# STM32_Nucleo_144.net
KiCad netlist of a schematic drawn in Altium Designer
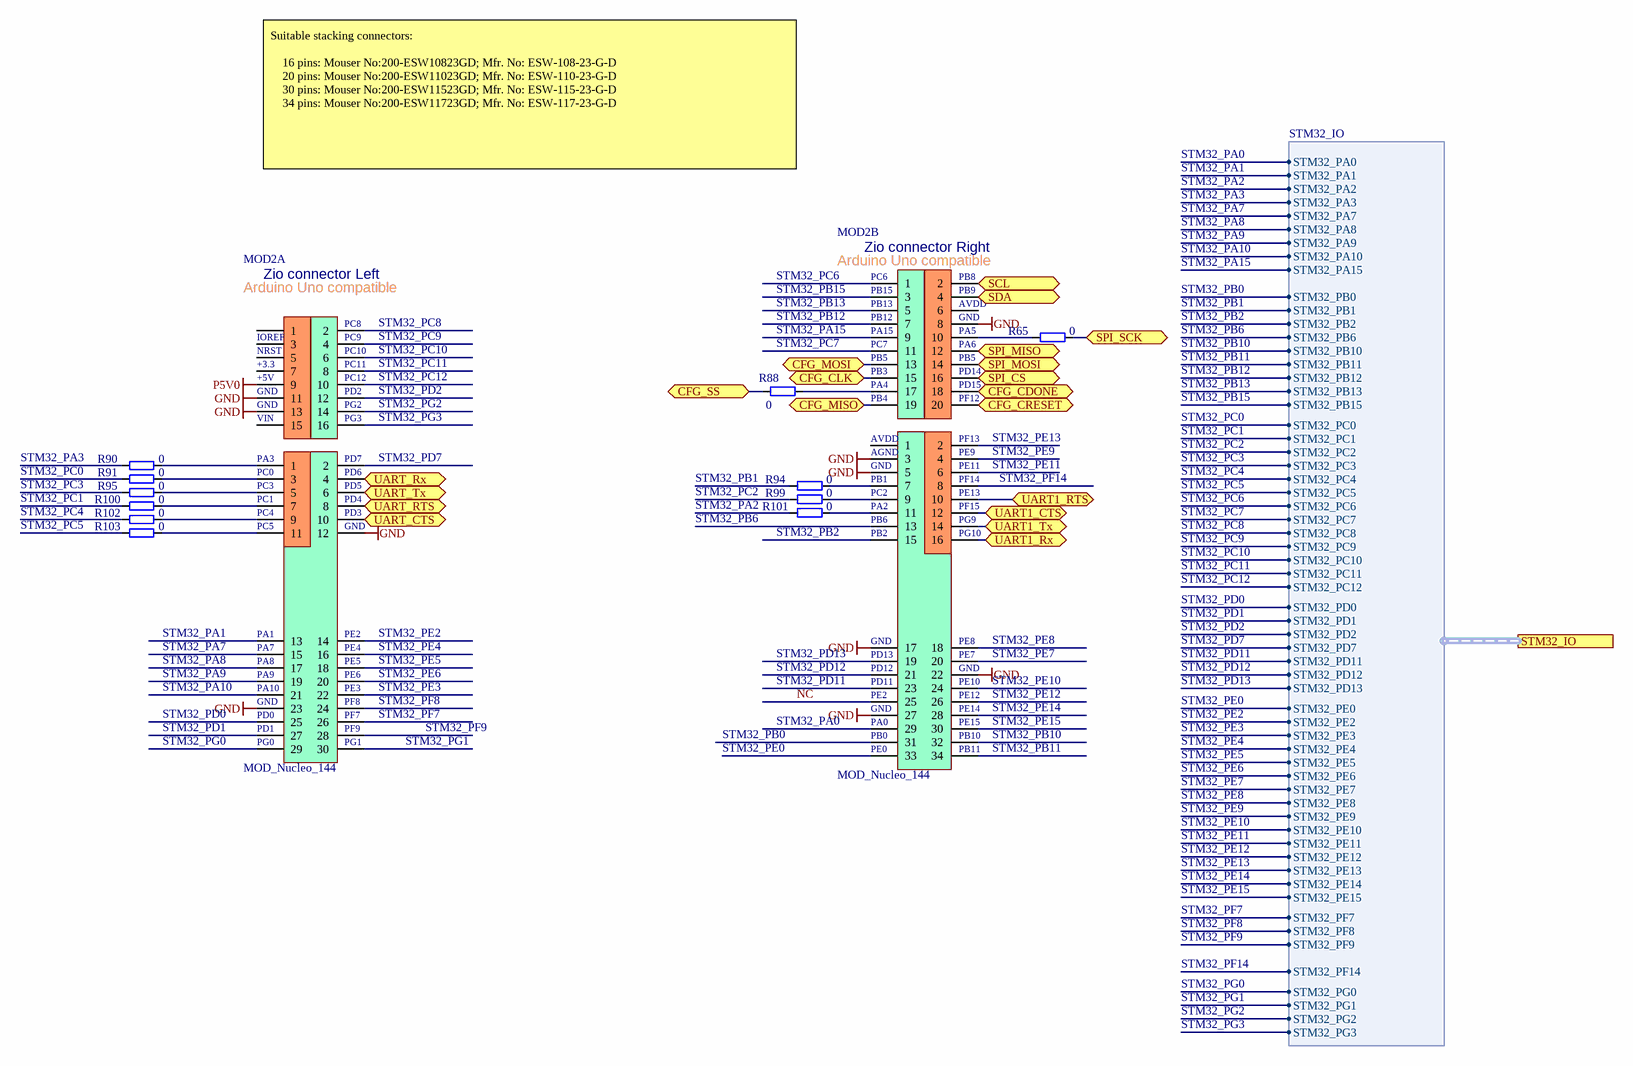
[diagram p0: STM32_Nucleo_144.SchDoc]

(export (version "E")
  (design (tool "Eeschema 10.0.6"))
  (components
    (comp (ref "MOD2")
      (value "MOD_Nucleo_144")
      (footprint "MOD_STM32_Nucleo_144")
      (libsource (lib "LIBRARY_SCH") (part "MOD_Nucleo_144"))
    )
    (comp (ref "R65")
      (value "0")
      (footprint "RESC1608X55N")
      (description "Resistor")
      (fields
        (field (name "PART NUMBER") "R0603_0R_JUMPER")
        (field (name "MANUFACTURER") "GENERIC")
        (field (name "AUTHOR") "CERN DEM JLC")
      )
      (libsource (lib "Resistors") (part "Resistor"))
    )
    (comp (ref "R88")
      (value "0")
      (footprint "RESC1608X55N")
      (description "Resistor")
      (fields
        (field (name "PART NUMBER") "R0603_0R_JUMPER")
        (field (name "MANUFACTURER") "GENERIC")
        (field (name "AUTHOR") "CERN DEM JLC")
      )
      (libsource (lib "Resistors") (part "Resistor"))
    )
    (comp (ref "R90")
      (value "0")
      (footprint "RESC1608X55N")
      (description "Resistor")
      (fields
        (field (name "PART NUMBER") "R0603_0R_JUMPER")
        (field (name "MANUFACTURER") "GENERIC")
        (field (name "AUTHOR") "CERN DEM JLC")
      )
      (libsource (lib "Resistors") (part "Resistor"))
    )
    (comp (ref "R91")
      (value "0")
      (footprint "RESC1608X55N")
      (description "Resistor")
      (fields
        (field (name "PART NUMBER") "R0603_0R_JUMPER")
        (field (name "MANUFACTURER") "GENERIC")
        (field (name "AUTHOR") "CERN DEM JLC")
      )
      (libsource (lib "Resistors") (part "Resistor"))
    )
    (comp (ref "R94")
      (value "0")
      (footprint "RESC1608X55N")
      (description "Resistor")
      (fields
        (field (name "PART NUMBER") "R0603_0R_JUMPER")
        (field (name "MANUFACTURER") "GENERIC")
        (field (name "AUTHOR") "CERN DEM JLC")
      )
      (libsource (lib "Resistors") (part "Resistor"))
    )
    (comp (ref "R95")
      (value "0")
      (footprint "RESC1608X55N")
      (description "Resistor")
      (fields
        (field (name "PART NUMBER") "R0603_0R_JUMPER")
        (field (name "MANUFACTURER") "GENERIC")
        (field (name "AUTHOR") "CERN DEM JLC")
      )
      (libsource (lib "Resistors") (part "Resistor"))
    )
    (comp (ref "R99")
      (value "0")
      (footprint "RESC1608X55N")
      (description "Resistor")
      (fields
        (field (name "PART NUMBER") "R0603_0R_JUMPER")
        (field (name "MANUFACTURER") "GENERIC")
        (field (name "AUTHOR") "CERN DEM JLC")
      )
      (libsource (lib "Resistors") (part "Resistor"))
    )
    (comp (ref "R100")
      (value "0")
      (footprint "RESC1608X55N")
      (description "Resistor")
      (fields
        (field (name "PART NUMBER") "R0603_0R_JUMPER")
        (field (name "MANUFACTURER") "GENERIC")
        (field (name "AUTHOR") "CERN DEM JLC")
      )
      (libsource (lib "Resistors") (part "Resistor"))
    )
    (comp (ref "R101")
      (value "0")
      (footprint "RESC1608X55N")
      (description "Resistor")
      (fields
        (field (name "PART NUMBER") "R0603_0R_JUMPER")
        (field (name "MANUFACTURER") "GENERIC")
        (field (name "AUTHOR") "CERN DEM JLC")
      )
      (libsource (lib "Resistors") (part "Resistor"))
    )
    (comp (ref "R102")
      (value "0")
      (footprint "RESC1608X55N")
      (description "Resistor")
      (fields
        (field (name "PART NUMBER") "R0603_0R_JUMPER")
        (field (name "MANUFACTURER") "GENERIC")
        (field (name "AUTHOR") "CERN DEM JLC")
      )
      (libsource (lib "Resistors") (part "Resistor"))
    )
    (comp (ref "R103")
      (value "0")
      (footprint "RESC1608X55N")
      (description "Resistor")
      (fields
        (field (name "PART NUMBER") "R0603_0R_JUMPER")
        (field (name "MANUFACTURER") "GENERIC")
        (field (name "AUTHOR") "CERN DEM JLC")
      )
      (libsource (lib "Resistors") (part "Resistor"))
    )
  )
  (nets
    (net (code "2") (name "/CFG_CDONE") (class "Default")
      (node (ref "MOD2") (pin "18c") (pinfunction "18_18c") (pintype "passive"))
    )
    (net (code "3") (name "/CFG_CLK") (class "Default")
      (node (ref "MOD2") (pin "15c") (pinfunction "15_15c") (pintype "passive"))
    )
    (net (code "4") (name "/CFG_CRESET") (class "Default")
      (node (ref "MOD2") (pin "20c") (pinfunction "20_20c") (pintype "passive"))
    )
    (net (code "5") (name "/CFG_MISO") (class "Default")
      (node (ref "MOD2") (pin "19c") (pinfunction "19_19c") (pintype "passive"))
    )
    (net (code "6") (name "/CFG_MOSI") (class "Default")
      (node (ref "MOD2") (pin "13c") (pinfunction "13_13c") (pintype "passive"))
    )
    (net (code "7") (name "/CFG_SS") (class "Default")
      (node (ref "R88") (pin "1") (pinfunction "1_1") (pintype "passive"))
    )
    (net (code "8") (name "/NC") (class "Default")
      (node (ref "MOD2") (pin "25d") (pinfunction "25_25d") (pintype "passive"))
    )
    (net (code "9") (name "/SCL") (class "Default")
      (node (ref "MOD2") (pin "2c") (pinfunction "2_2c") (pintype "passive"))
    )
    (net (code "10") (name "/SDA") (class "Default")
      (node (ref "MOD2") (pin "4c") (pinfunction "4_4c") (pintype "passive"))
    )
    (net (code "11") (name "/SPI_CS") (class "Default")
      (node (ref "MOD2") (pin "16c") (pinfunction "16_16c") (pintype "passive"))
    )
    (net (code "12") (name "/SPI_MISO") (class "Default")
      (node (ref "MOD2") (pin "12c") (pinfunction "12_12c") (pintype "passive"))
    )
    (net (code "13") (name "/SPI_MOSI") (class "Default")
      (node (ref "MOD2") (pin "14c") (pinfunction "14_14c") (pintype "passive"))
    )
    (net (code "14") (name "/SPI_SCK") (class "Default")
      (node (ref "R65") (pin "2") (pinfunction "2_2") (pintype "passive"))
    )
    (net (code "15") (name "/STM32_PA0") (class "Default")
      (node (ref "MOD2") (pin "29d") (pinfunction "29_29d") (pintype "passive"))
    )
    (net (code "16") (name "/STM32_PA1") (class "Default")
      (node (ref "MOD2") (pin "13b") (pinfunction "13_13b") (pintype "passive"))
    )
    (net (code "17") (name "/STM32_PA2") (class "Default")
      (node (ref "R101") (pin "1") (pinfunction "1_1") (pintype "passive"))
    )
    (net (code "18") (name "/STM32_PA3") (class "Default")
      (node (ref "R90") (pin "1") (pinfunction "1_1") (pintype "passive"))
    )
    (net (code "19") (name "/STM32_PA7") (class "Default")
      (node (ref "MOD2") (pin "15b") (pinfunction "15_15b") (pintype "passive"))
    )
    (net (code "20") (name "/STM32_PA8") (class "Default")
      (node (ref "MOD2") (pin "17b") (pinfunction "17_17b") (pintype "passive"))
    )
    (net (code "21") (name "/STM32_PA9") (class "Default")
      (node (ref "MOD2") (pin "19b") (pinfunction "19_19b") (pintype "passive"))
    )
    (net (code "22") (name "/STM32_PA10") (class "Default")
      (node (ref "MOD2") (pin "21b") (pinfunction "21_21b") (pintype "passive"))
    )
    (net (code "23") (name "/STM32_PA15") (class "Default")
      (node (ref "MOD2") (pin "9c") (pinfunction "9_9c") (pintype "passive"))
    )
    (net (code "24") (name "/STM32_PB0") (class "Default")
      (node (ref "MOD2") (pin "31d") (pinfunction "31_31d") (pintype "passive"))
    )
    (net (code "25") (name "/STM32_PB1") (class "Default")
      (node (ref "R94") (pin "1") (pinfunction "1_1") (pintype "passive"))
    )
    (net (code "26") (name "/STM32_PB2") (class "Default")
      (node (ref "MOD2") (pin "15d") (pinfunction "15_15d") (pintype "passive"))
    )
    (net (code "27") (name "/STM32_PB6") (class "Default")
      (node (ref "MOD2") (pin "13d") (pinfunction "13_13d") (pintype "passive"))
    )
    (net (code "28") (name "/STM32_PB10") (class "Default")
      (node (ref "MOD2") (pin "32d") (pinfunction "32_32d") (pintype "passive"))
    )
    (net (code "29") (name "/STM32_PB11") (class "Default")
      (node (ref "MOD2") (pin "34d") (pinfunction "34_34d") (pintype "passive"))
    )
    (net (code "30") (name "/STM32_PB12") (class "Default")
      (node (ref "MOD2") (pin "7c") (pinfunction "7_7c") (pintype "passive"))
    )
    (net (code "31") (name "/STM32_PB13") (class "Default")
      (node (ref "MOD2") (pin "5c") (pinfunction "5_5c") (pintype "passive"))
    )
    (net (code "32") (name "/STM32_PB15") (class "Default")
      (node (ref "MOD2") (pin "3c") (pinfunction "3_3c") (pintype "passive"))
    )
    (net (code "33") (name "/STM32_PC0") (class "Default")
      (node (ref "R91") (pin "1") (pinfunction "1_1") (pintype "passive"))
    )
    (net (code "34") (name "/STM32_PC1") (class "Default")
      (node (ref "R100") (pin "1") (pinfunction "1_1") (pintype "passive"))
    )
    (net (code "35") (name "/STM32_PC2") (class "Default")
      (node (ref "R99") (pin "1") (pinfunction "1_1") (pintype "passive"))
    )
    (net (code "36") (name "/STM32_PC3") (class "Default")
      (node (ref "R95") (pin "1") (pinfunction "1_1") (pintype "passive"))
    )
    (net (code "37") (name "/STM32_PC4") (class "Default")
      (node (ref "R102") (pin "1") (pinfunction "1_1") (pintype "passive"))
    )
    (net (code "38") (name "/STM32_PC5") (class "Default")
      (node (ref "R103") (pin "1") (pinfunction "1_1") (pintype "passive"))
    )
    (net (code "39") (name "/STM32_PC6") (class "Default")
      (node (ref "MOD2") (pin "1c") (pinfunction "1_1c") (pintype "passive"))
    )
    (net (code "40") (name "/STM32_PC7") (class "Default")
      (node (ref "MOD2") (pin "11c") (pinfunction "11_11c") (pintype "passive"))
    )
    (net (code "41") (name "/STM32_PC8") (class "Default")
      (node (ref "MOD2") (pin "2a") (pinfunction "2_2a") (pintype "passive"))
    )
    (net (code "42") (name "/STM32_PC9") (class "Default")
      (node (ref "MOD2") (pin "4a") (pinfunction "4_4a") (pintype "passive"))
    )
    (net (code "43") (name "/STM32_PC10") (class "Default")
      (node (ref "MOD2") (pin "6a") (pinfunction "6_6a") (pintype "passive"))
    )
    (net (code "44") (name "/STM32_PC11") (class "Default")
      (node (ref "MOD2") (pin "8a") (pinfunction "8_8a") (pintype "passive"))
    )
    (net (code "45") (name "/STM32_PC12") (class "Default")
      (node (ref "MOD2") (pin "10a") (pinfunction "10_10a") (pintype "passive"))
    )
    (net (code "46") (name "/STM32_PD0") (class "Default")
      (node (ref "MOD2") (pin "25b") (pinfunction "25_25b") (pintype "passive"))
    )
    (net (code "47") (name "/STM32_PD1") (class "Default")
      (node (ref "MOD2") (pin "27b") (pinfunction "27_27b") (pintype "passive"))
    )
    (net (code "48") (name "/STM32_PD2") (class "Default")
      (node (ref "MOD2") (pin "12a") (pinfunction "12_12a") (pintype "passive"))
    )
    (net (code "49") (name "/STM32_PD7") (class "Default")
      (node (ref "MOD2") (pin "2b") (pinfunction "2_2b") (pintype "passive"))
    )
    (net (code "50") (name "/STM32_PD11") (class "Default")
      (node (ref "MOD2") (pin "23d") (pinfunction "23_23d") (pintype "passive"))
    )
    (net (code "51") (name "/STM32_PD12") (class "Default")
      (node (ref "MOD2") (pin "21d") (pinfunction "21_21d") (pintype "passive"))
    )
    (net (code "52") (name "/STM32_PD13") (class "Default")
      (node (ref "MOD2") (pin "19d") (pinfunction "19_19d") (pintype "passive"))
    )
    (net (code "53") (name "/STM32_PE0") (class "Default")
      (node (ref "MOD2") (pin "33d") (pinfunction "33_33d") (pintype "passive"))
    )
    (net (code "54") (name "/STM32_PE2") (class "Default")
      (node (ref "MOD2") (pin "14b") (pinfunction "14_14b") (pintype "passive"))
    )
    (net (code "55") (name "/STM32_PE3") (class "Default")
      (node (ref "MOD2") (pin "22b") (pinfunction "22_22b") (pintype "passive"))
    )
    (net (code "56") (name "/STM32_PE4") (class "Default")
      (node (ref "MOD2") (pin "16b") (pinfunction "16_16b") (pintype "passive"))
    )
    (net (code "57") (name "/STM32_PE5") (class "Default")
      (node (ref "MOD2") (pin "18b") (pinfunction "18_18b") (pintype "passive"))
    )
    (net (code "58") (name "/STM32_PE6") (class "Default")
      (node (ref "MOD2") (pin "20b") (pinfunction "20_20b") (pintype "passive"))
    )
    (net (code "59") (name "/STM32_PE7") (class "Default")
      (node (ref "MOD2") (pin "20d") (pinfunction "20_20d") (pintype "passive"))
    )
    (net (code "60") (name "/STM32_PE8") (class "Default")
      (node (ref "MOD2") (pin "18d") (pinfunction "18_18d") (pintype "passive"))
    )
    (net (code "61") (name "/STM32_PE9") (class "Default")
      (node (ref "MOD2") (pin "4d") (pinfunction "4_4d") (pintype "passive"))
    )
    (net (code "62") (name "/STM32_PE10") (class "Default")
      (node (ref "MOD2") (pin "24d") (pinfunction "24_24d") (pintype "passive"))
    )
    (net (code "63") (name "/STM32_PE11") (class "Default")
      (node (ref "MOD2") (pin "6d") (pinfunction "6_6d") (pintype "passive"))
    )
    (net (code "64") (name "/STM32_PE12") (class "Default")
      (node (ref "MOD2") (pin "26d") (pinfunction "26_26d") (pintype "passive"))
    )
    (net (code "65") (name "/STM32_PE13") (class "Default")
      (node (ref "MOD2") (pin "2d") (pinfunction "2_2d") (pintype "passive"))
    )
    (net (code "66") (name "/STM32_PE14") (class "Default")
      (node (ref "MOD2") (pin "28d") (pinfunction "28_28d") (pintype "passive"))
    )
    (net (code "67") (name "/STM32_PE15") (class "Default")
      (node (ref "MOD2") (pin "30d") (pinfunction "30_30d") (pintype "passive"))
    )
    (net (code "68") (name "/STM32_PF7") (class "Default")
      (node (ref "MOD2") (pin "26b") (pinfunction "26_26b") (pintype "passive"))
    )
    (net (code "69") (name "/STM32_PF8") (class "Default")
      (node (ref "MOD2") (pin "24b") (pinfunction "24_24b") (pintype "passive"))
    )
    (net (code "70") (name "/STM32_PF9") (class "Default")
      (node (ref "MOD2") (pin "28b") (pinfunction "28_28b") (pintype "passive"))
    )
    (net (code "71") (name "/STM32_PF14") (class "Default")
      (node (ref "MOD2") (pin "8d") (pinfunction "8_8d") (pintype "passive"))
    )
    (net (code "72") (name "/STM32_PG0") (class "Default")
      (node (ref "MOD2") (pin "29b") (pinfunction "29_29b") (pintype "passive"))
    )
    (net (code "73") (name "/STM32_PG1") (class "Default")
      (node (ref "MOD2") (pin "30b") (pinfunction "30_30b") (pintype "passive"))
    )
    (net (code "74") (name "/STM32_PG2") (class "Default")
      (node (ref "MOD2") (pin "14a") (pinfunction "14_14a") (pintype "passive"))
    )
    (net (code "75") (name "/STM32_PG3") (class "Default")
      (node (ref "MOD2") (pin "16a") (pinfunction "16_16a") (pintype "passive"))
    )
    (net (code "76") (name "/UART1_CTS") (class "Default")
      (node (ref "MOD2") (pin "12d") (pinfunction "12_12d") (pintype "passive"))
    )
    (net (code "77") (name "/UART1_RTS") (class "Default")
      (node (ref "MOD2") (pin "10d") (pinfunction "10_10d") (pintype "passive"))
    )
    (net (code "78") (name "/UART1_Rx") (class "Default")
      (node (ref "MOD2") (pin "16d") (pinfunction "16_16d") (pintype "passive"))
    )
    (net (code "79") (name "/UART1_Tx") (class "Default")
      (node (ref "MOD2") (pin "14d") (pinfunction "14_14d") (pintype "passive"))
    )
    (net (code "80") (name "/UART_CTS") (class "Default")
      (node (ref "MOD2") (pin "10b") (pinfunction "10_10b") (pintype "passive"))
    )
    (net (code "81") (name "/UART_RTS") (class "Default")
      (node (ref "MOD2") (pin "8b") (pinfunction "8_8b") (pintype "passive"))
    )
    (net (code "82") (name "/UART_Rx") (class "Default")
      (node (ref "MOD2") (pin "4b") (pinfunction "4_4b") (pintype "passive"))
    )
    (net (code "83") (name "/UART_Tx") (class "Default")
      (node (ref "MOD2") (pin "6b") (pinfunction "6_6b") (pintype "passive"))
    )
    (net (code "85") (name "GND") (class "Default")
      (node (ref "MOD2") (pin "11a") (pinfunction "11_11a") (pintype "passive"))
      (node (ref "MOD2") (pin "12b") (pinfunction "12_12b") (pintype "passive"))
      (node (ref "MOD2") (pin "13a") (pinfunction "13_13a") (pintype "passive"))
      (node (ref "MOD2") (pin "17d") (pinfunction "17_17d") (pintype "passive"))
      (node (ref "MOD2") (pin "22d") (pinfunction "22_22d") (pintype "passive"))
      (node (ref "MOD2") (pin "23b") (pinfunction "23_23b") (pintype "passive"))
      (node (ref "MOD2") (pin "27d") (pinfunction "27_27d") (pintype "passive"))
      (node (ref "MOD2") (pin "3d") (pinfunction "3_3d") (pintype "passive"))
      (node (ref "MOD2") (pin "5d") (pinfunction "5_5d") (pintype "passive"))
      (node (ref "MOD2") (pin "8c") (pinfunction "8_8c") (pintype "passive"))
    )
    (net (code "86") (name "Net-(MOD2A-1-Pad1b)") (class "Default")
      (node (ref "MOD2") (pin "1b") (pinfunction "1_1b") (pintype "passive"))
      (node (ref "R90") (pin "2") (pinfunction "2_2") (pintype "passive"))
    )
    (net (code "87") (name "Net-(MOD2A-3-Pad3b)") (class "Default")
      (node (ref "MOD2") (pin "3b") (pinfunction "3_3b") (pintype "passive"))
      (node (ref "R91") (pin "2") (pinfunction "2_2") (pintype "passive"))
    )
    (net (code "88") (name "Net-(MOD2A-5-Pad5b)") (class "Default")
      (node (ref "MOD2") (pin "5b") (pinfunction "5_5b") (pintype "passive"))
      (node (ref "R95") (pin "2") (pinfunction "2_2") (pintype "passive"))
    )
    (net (code "89") (name "Net-(MOD2A-7-Pad7b)") (class "Default")
      (node (ref "MOD2") (pin "7b") (pinfunction "7_7b") (pintype "passive"))
      (node (ref "R100") (pin "2") (pinfunction "2_2") (pintype "passive"))
    )
    (net (code "90") (name "Net-(MOD2A-9-Pad9b)") (class "Default")
      (node (ref "MOD2") (pin "9b") (pinfunction "9_9b") (pintype "passive"))
      (node (ref "R102") (pin "2") (pinfunction "2_2") (pintype "passive"))
    )
    (net (code "91") (name "Net-(MOD2A-11-Pad11b)") (class "Default")
      (node (ref "MOD2") (pin "11b") (pinfunction "11_11b") (pintype "passive"))
      (node (ref "R103") (pin "2") (pinfunction "2_2") (pintype "passive"))
    )
    (net (code "92") (name "Net-(MOD2B-7-Pad7d)") (class "Default")
      (node (ref "MOD2") (pin "7d") (pinfunction "7_7d") (pintype "passive"))
      (node (ref "R94") (pin "2") (pinfunction "2_2") (pintype "passive"))
    )
    (net (code "93") (name "Net-(MOD2B-9-Pad9d)") (class "Default")
      (node (ref "MOD2") (pin "9d") (pinfunction "9_9d") (pintype "passive"))
      (node (ref "R99") (pin "2") (pinfunction "2_2") (pintype "passive"))
    )
    (net (code "94") (name "Net-(MOD2B-10-Pad10c)") (class "Default")
      (node (ref "MOD2") (pin "10c") (pinfunction "10_10c") (pintype "passive"))
      (node (ref "R65") (pin "1") (pinfunction "1_1") (pintype "passive"))
    )
    (net (code "95") (name "Net-(MOD2B-11-Pad11d)") (class "Default")
      (node (ref "MOD2") (pin "11d") (pinfunction "11_11d") (pintype "passive"))
      (node (ref "R101") (pin "2") (pinfunction "2_2") (pintype "passive"))
    )
    (net (code "96") (name "Net-(MOD2B-17-Pad17c)") (class "Default")
      (node (ref "MOD2") (pin "17c") (pinfunction "17_17c") (pintype "passive"))
      (node (ref "R88") (pin "2") (pinfunction "2_2") (pintype "passive"))
    )
    (net (code "97") (name "P5V0") (class "Default")
      (node (ref "MOD2") (pin "9a") (pinfunction "9_9a") (pintype "passive"))
    )
    (net (code "98") (name "unconnected-(MOD2A-1-Pad1a)") (class "Default")
      (node (ref "MOD2") (pin "1a") (pinfunction "1_1a") (pintype "passive"))
    )
    (net (code "99") (name "unconnected-(MOD2A-3-Pad3a)") (class "Default")
      (node (ref "MOD2") (pin "3a") (pinfunction "3_3a") (pintype "passive"))
    )
    (net (code "100") (name "unconnected-(MOD2A-5-Pad5a)") (class "Default")
      (node (ref "MOD2") (pin "5a") (pinfunction "5_5a") (pintype "passive"))
    )
    (net (code "101") (name "unconnected-(MOD2A-7-Pad7a)") (class "Default")
      (node (ref "MOD2") (pin "7a") (pinfunction "7_7a") (pintype "passive"))
    )
    (net (code "102") (name "unconnected-(MOD2A-15-Pad15a)") (class "Default")
      (node (ref "MOD2") (pin "15a") (pinfunction "15_15a") (pintype "passive"))
    )
    (net (code "103") (name "unconnected-(MOD2B-1-Pad1d)") (class "Default")
      (node (ref "MOD2") (pin "1d") (pinfunction "1_1d") (pintype "passive"))
    )
    (net (code "104") (name "unconnected-(MOD2B-6-Pad6c)") (class "Default")
      (node (ref "MOD2") (pin "6c") (pinfunction "6_6c") (pintype "passive"))
    )
  )
)
